# Sheet1.net
KiCad netlist of a schematic drawn in Altium Designer
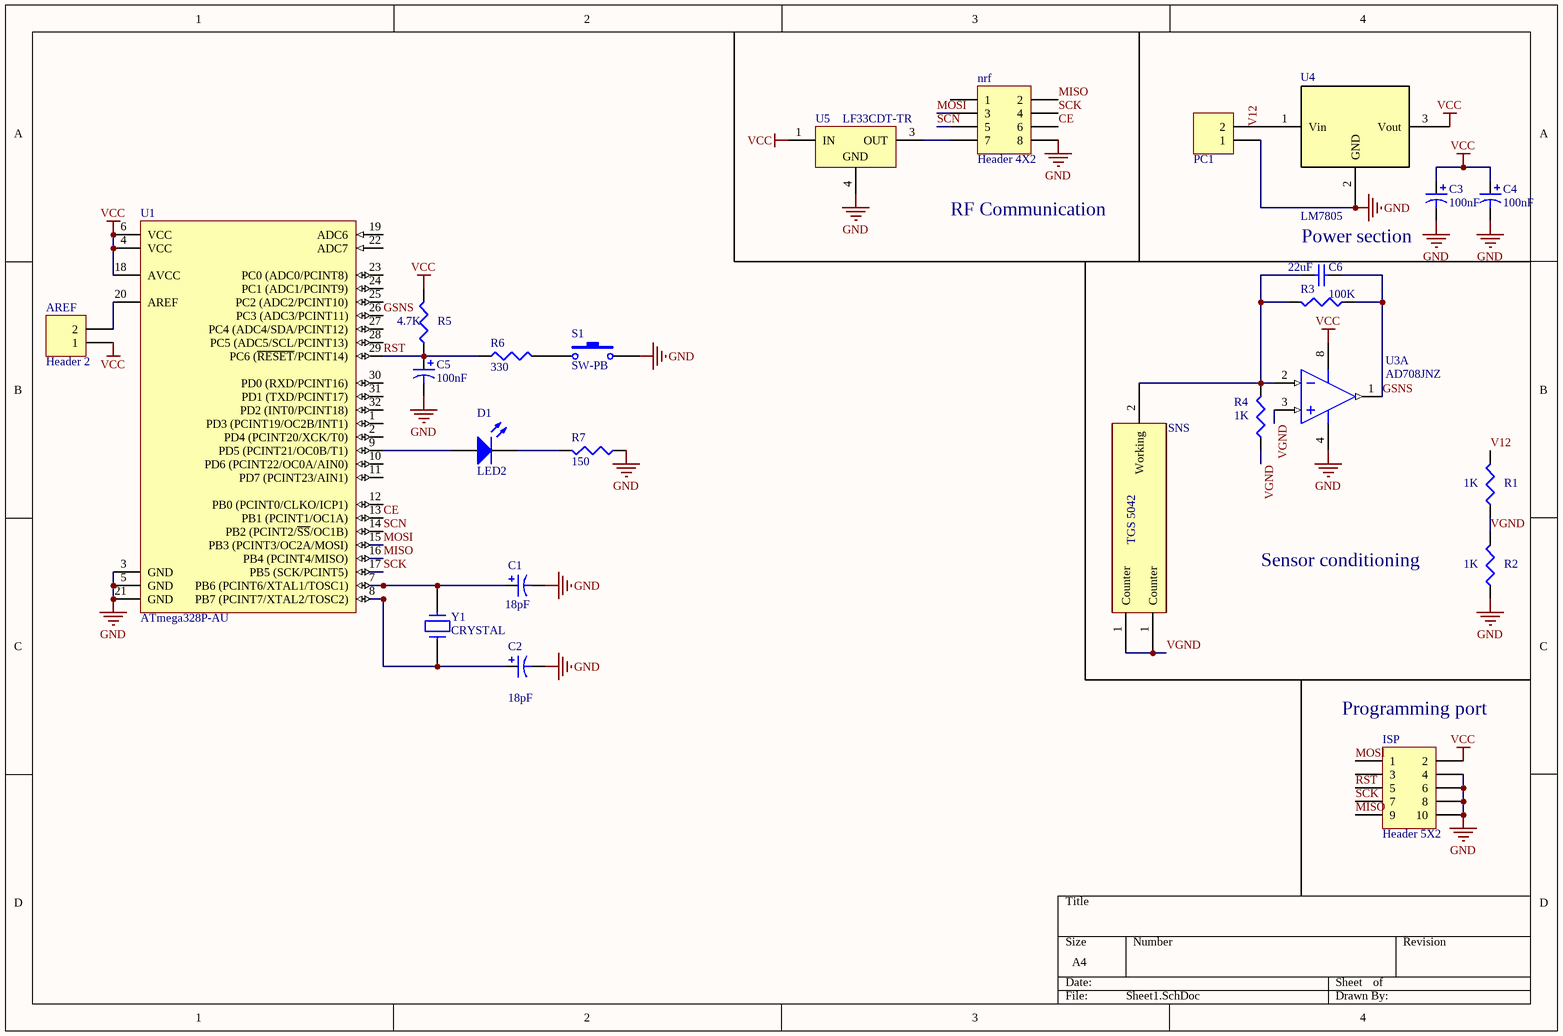
[diagram p0: Sheet1.SchDoc]

(export (version "E")
  (design (tool "Eeschema 10.0.6"))
  (components
    (comp (ref "AREF")
      (value "Header 2")
      (footprint "HDR1X2")
      (description "Header, 2-Pin")
      (fields (field (name "PUBLISHER") "Altium Limited"))
      (libsource (lib "IOT_UNI_VER1") (part "Header 2"))
    )
    (comp (ref "C1")
      (value "18pF")
      (footprint "Resistor")
      (description "Polarized Capacitor (Surface Mount)")
      (fields (field (name "Comment") "Cap Pol3") (field (name "PUBLISHER") "Altium Limited"))
      (libsource (lib "IOT_UNI_VER1") (part "Cap Pol3"))
    )
    (comp (ref "C2")
      (value "18pF")
      (footprint "Resistor")
      (description "Polarized Capacitor (Surface Mount)")
      (fields (field (name "Comment") "Cap Pol3") (field (name "PUBLISHER") "Altium Limited"))
      (libsource (lib "IOT_UNI_VER1") (part "Cap Pol3"))
    )
    (comp (ref "C3")
      (value "100nF")
      (footprint "Resistor")
      (description "Polarized Capacitor (Surface Mount)")
      (fields (field (name "Comment") "Cap Pol3") (field (name "PUBLISHER") "Altium Limited"))
      (libsource (lib "IOT_UNI_VER1") (part "Cap Pol3"))
    )
    (comp (ref "C4")
      (value "100nF")
      (footprint "Resistor")
      (description "Polarized Capacitor (Surface Mount)")
      (fields (field (name "Comment") "Cap Pol3") (field (name "PUBLISHER") "Altium Limited"))
      (libsource (lib "IOT_UNI_VER1") (part "Cap Pol3"))
    )
    (comp (ref "C5")
      (value "100nF")
      (footprint "Resistor")
      (description "Polarized Capacitor (Surface Mount)")
      (fields (field (name "Comment") "Cap Pol3") (field (name "PUBLISHER") "Altium Limited"))
      (libsource (lib "IOT_UNI_VER1") (part "Cap Pol3"))
    )
    (comp (ref "C6")
      (value "22uF")
      (footprint "RB.1/.3")
      (description "Capacitor (Semiconductor SIM Model)")
      (fields (field (name "PUBLISHER") "Altium Limited"))
      (libsource (lib "Devices") (part "Cap Semi"))
    )
    (comp (ref "D1")
      (value "LED2")
      (footprint "3.2X1.6X1.1")
      (description "Typical RED, GREEN, YELLOW, AMBER GaAs LED")
      (fields (field (name "PUBLISHER") "Altium Limited"))
      (libsource (lib "Miscellaneous Devices") (part "LED2"))
    )
    (comp (ref "ISP")
      (value "Header 5X2")
      (footprint "HDR2X5")
      (description "Header, 5-Pin, Dual row")
      (fields (field (name "PUBLISHER") "Altium Limited"))
      (libsource (lib "IOT_UNI_VER1") (part "Header 5X2"))
    )
    (comp (ref "nrf")
      (value "Header 4X2")
      (footprint "HDR2X4")
      (description "Header, 4-Pin, Dual row")
      (fields (field (name "PUBLISHER") "Altium Limited"))
      (libsource (lib "IOT_UNI_VER1") (part "Header 4X2"))
    )
    (comp (ref "PC1")
      (value "Power Connector")
      (footprint "My_ Power_Connector")
      (description "white Power Connector")
      (libsource (lib "Altium library (www.AVRelec.com)") (part "Power Connector"))
    )
    (comp (ref "R1")
      (value "1K")
      (footprint "Resistor")
      (description "Resistor")
      (fields (field (name "Comment") "Rsepehr") (field (name "PUBLISHER") "Altium Limited"))
      (libsource (lib "IOT_UNI_VER1") (part "Res3"))
    )
    (comp (ref "R2")
      (value "1K")
      (footprint "Resistor")
      (description "Resistor")
      (fields (field (name "Comment") "Rsepehr") (field (name "PUBLISHER") "Altium Limited"))
      (libsource (lib "IOT_UNI_VER1") (part "Res3"))
    )
    (comp (ref "R3")
      (value "100K")
      (footprint "Resistor")
      (description "Resistor")
      (fields (field (name "Comment") "Rsepehr") (field (name "PUBLISHER") "Altium Limited"))
      (libsource (lib "IOT_UNI_VER1") (part "Res3"))
    )
    (comp (ref "R4")
      (value "1K")
      (footprint "Resistor")
      (description "Resistor")
      (fields (field (name "Comment") "Rsepehr") (field (name "PUBLISHER") "Altium Limited"))
      (libsource (lib "IOT_UNI_VER1") (part "Res3"))
    )
    (comp (ref "R5")
      (value "4.7K")
      (footprint "Resistor")
      (description "Resistor")
      (fields (field (name "Comment") "Rsepehr") (field (name "PUBLISHER") "Altium Limited"))
      (libsource (lib "IOT_UNI_VER1") (part "Res3"))
    )
    (comp (ref "R6")
      (value "330")
      (footprint "Resistor")
      (description "Resistor")
      (fields (field (name "Comment") "Rsepehr") (field (name "PUBLISHER") "Altium Limited"))
      (libsource (lib "IOT_UNI_VER1") (part "Res3"))
    )
    (comp (ref "R7")
      (value "150")
      (footprint "Resistor")
      (description "Resistor")
      (fields (field (name "Comment") "Rsepehr") (field (name "PUBLISHER") "Altium Limited"))
      (libsource (lib "IOT_UNI_VER1") (part "Res3"))
    )
    (comp (ref "S1")
      (value "SW-PB")
      (footprint "SPST-2")
      (description "Switch")
      (fields (field (name "PUBLISHER") "Altium Limited"))
      (libsource (lib "Miscellaneous Devices") (part "SW-PB"))
    )
    (comp (ref "SNS")
      (value "Component_1")
      (footprint "GSPAK")
      (libsource (lib "TGS 5042") (part "Component_1"))
    )
    (comp (ref "U1")
      (value "ATmega328P-AU")
      (footprint "32A_N")
      (libsource (lib "Atmel Microcontroller megaAVR") (part "ATmega328P-AU"))
    )
    (comp (ref "U3")
      (value "AD708JNZ")
      (footprint "ADI-N-8")
      (fields (field (name "GENERIC PART NUMBER") "AD708") (field (name "MANUFACTURER") "Analog Devices"))
      (libsource (lib "Analog Devices Operational Amplifiers") (part "AD708JNZ"))
    )
    (comp (ref "U4") (value "LM7805") (footprint "TO-220") (libsource (lib "LM7805") (part "Component_1")))
    (comp (ref "U5")
      (value "LF33CDT-TR")
      (footprint "TO-252_N")
      (description "500mA, Very Low Drop (0.45V) Voltage Regulator, 3.3V, 3-Pin DPAK, Tape and Reel")
      (libsource (lib "STMicroelectronics Power Management Linear Regulator") (part "LF33CDT-TR"))
    )
    (comp (ref "Y1")
      (value "CRYSTAL")
      (footprint "My_Crystal")
      (description "Crystal")
      (libsource (lib "IOT_UNI_VER1") (part "CRYSTAL"))
    )
  )
  (nets
    (net (code "1") (name "/CE") (class "Default")
      (node (ref "U1") (pin "13") (pinfunction "PB1_(PCINT1/OC1A)_13") (pintype "bidirectional"))
      (node (ref "nrf") (pin "6") (pinfunction "6_6") (pintype "passive"))
    )
    (net (code "2") (name "/GSNS") (class "Default")
      (node (ref "C6") (pin "2") (pinfunction "2_2") (pintype "passive"))
      (node (ref "R3") (pin "1") (pinfunction "1_1") (pintype "passive"))
      (node (ref "U1") (pin "26") (pinfunction "PC3_(ADC3/PCINT11)_26") (pintype "bidirectional"))
      (node (ref "U3") (pin "1") (pinfunction "OUT_A_1") (pintype "output"))
    )
    (net (code "3") (name "/MISO") (class "Default")
      (node (ref "ISP") (pin "9") (pinfunction "9_9") (pintype "passive"))
      (node (ref "U1") (pin "16") (pinfunction "PB4_(PCINT4/MISO)_16") (pintype "bidirectional"))
      (node (ref "nrf") (pin "2") (pinfunction "2_2") (pintype "passive"))
    )
    (net (code "4") (name "/MOSI") (class "Default")
      (node (ref "ISP") (pin "1") (pinfunction "1_1") (pintype "passive"))
      (node (ref "U1") (pin "15") (pinfunction "PB3_(PCINT3/OC2A/MOSI)_15") (pintype "bidirectional"))
      (node (ref "nrf") (pin "3") (pinfunction "3_3") (pintype "passive"))
    )
    (net (code "5") (name "/RST") (class "Default")
      (node (ref "C5") (pin "1") (pinfunction "1_1") (pintype "passive"))
      (node (ref "ISP") (pin "5") (pinfunction "5_5") (pintype "passive"))
      (node (ref "R5") (pin "1") (pinfunction "1_1") (pintype "passive"))
      (node (ref "R6") (pin "1") (pinfunction "1_1") (pintype "passive"))
      (node (ref "U1") (pin "29") (pinfunction "PC6_(~{RESET}/PCINT14)_29") (pintype "bidirectional"))
    )
    (net (code "6") (name "/SCK") (class "Default")
      (node (ref "ISP") (pin "7") (pinfunction "7_7") (pintype "passive"))
      (node (ref "U1") (pin "17") (pinfunction "PB5_(SCK/PCINT5)_17") (pintype "bidirectional"))
      (node (ref "nrf") (pin "4") (pinfunction "4_4") (pintype "passive"))
    )
    (net (code "7") (name "/SCN") (class "Default")
      (node (ref "U1") (pin "14") (pinfunction "PB2_(PCINT2/~{SS}/OC1B)_14") (pintype "bidirectional"))
      (node (ref "nrf") (pin "5") (pinfunction "5_5") (pintype "passive"))
    )
    (net (code "8") (name "/V12") (class "Default")
      (node (ref "PC1") (pin "2") (pinfunction "2_2") (pintype "passive"))
      (node (ref "R1") (pin "2") (pinfunction "2_2") (pintype "passive"))
      (node (ref "U4") (pin "1") (pinfunction "Vin_1") (pintype "passive"))
    )
    (net (code "9") (name "/VGND") (class "Default")
      (node (ref "R1") (pin "1") (pinfunction "1_1") (pintype "passive"))
      (node (ref "R2") (pin "2") (pinfunction "2_2") (pintype "passive"))
      (node (ref "R4") (pin "1") (pinfunction "1_1") (pintype "passive"))
      (node (ref "SNS") (pin "1") (pinfunction "Counter_1") (pintype "passive"))
      (node (ref "U3") (pin "3") (pinfunction "+IN_A_3") (pintype "input"))
    )
    (net (code "10") (name "GND") (class "Default")
      (node (ref "C1") (pin "2") (pinfunction "2_2") (pintype "passive"))
      (node (ref "C2") (pin "2") (pinfunction "2_2") (pintype "passive"))
      (node (ref "C3") (pin "2") (pinfunction "2_2") (pintype "passive"))
      (node (ref "C4") (pin "2") (pinfunction "2_2") (pintype "passive"))
      (node (ref "C5") (pin "2") (pinfunction "2_2") (pintype "passive"))
      (node (ref "ISP") (pin "10") (pinfunction "10_10") (pintype "passive"))
      (node (ref "ISP") (pin "4") (pinfunction "4_4") (pintype "passive"))
      (node (ref "ISP") (pin "6") (pinfunction "6_6") (pintype "passive"))
      (node (ref "ISP") (pin "8") (pinfunction "8_8") (pintype "passive"))
      (node (ref "PC1") (pin "1") (pinfunction "1_1") (pintype "passive"))
      (node (ref "R2") (pin "1") (pinfunction "1_1") (pintype "passive"))
      (node (ref "R7") (pin "1") (pinfunction "1_1") (pintype "passive"))
      (node (ref "S1") (pin "2") (pinfunction "2_2") (pintype "passive"))
      (node (ref "U1") (pin "21") (pinfunction "GND_21") (pintype "power_in"))
      (node (ref "U1") (pin "3") (pinfunction "GND_3") (pintype "power_in"))
      (node (ref "U1") (pin "5") (pinfunction "GND_5") (pintype "power_in"))
      (node (ref "U3") (pin "4") (pinfunction "-VS_4") (pintype "power_in"))
      (node (ref "U4") (pin "2") (pinfunction "GND_2") (pintype "passive"))
      (node (ref "U5") (pin "4") (pinfunction "GND_4") (pintype "power_in"))
      (node (ref "nrf") (pin "8") (pinfunction "8_8") (pintype "passive"))
    )
    (net (code "11") (name "Net-(D1-A)") (class "Default")
      (node (ref "D1") (pin "1") (pinfunction "A_1") (pintype "passive"))
      (node (ref "U1") (pin "9") (pinfunction "PD5_(PCINT21/OC0B/T1)_9") (pintype "bidirectional"))
    )
    (net (code "12") (name "Net-(D1-K)") (class "Default")
      (node (ref "D1") (pin "2") (pinfunction "K_2") (pintype "passive"))
      (node (ref "R7") (pin "2") (pinfunction "2_2") (pintype "passive"))
    )
    (net (code "13") (name "Net-(R6-Pad2)") (class "Default")
      (node (ref "R6") (pin "2") (pinfunction "2_2") (pintype "passive"))
      (node (ref "S1") (pin "1") (pinfunction "1_1") (pintype "passive"))
    )
    (net (code "14") (name "Net-(SNS-Working)") (class "Default")
      (node (ref "C6") (pin "1") (pinfunction "1_1") (pintype "passive"))
      (node (ref "R3") (pin "2") (pinfunction "2_2") (pintype "passive"))
      (node (ref "R4") (pin "2") (pinfunction "2_2") (pintype "passive"))
      (node (ref "SNS") (pin "2") (pinfunction "Working_2") (pintype "passive"))
      (node (ref "U3") (pin "2") (pinfunction "-IN_A_2") (pintype "input"))
    )
    (net (code "15") (name "Net-(U1-AREF)") (class "Default")
      (node (ref "AREF") (pin "2") (pinfunction "2_2") (pintype "passive"))
      (node (ref "U1") (pin "20") (pinfunction "AREF_20") (pintype "passive"))
    )
    (net (code "16") (name "Net-(U1-PB6_(PCINT6{slash}XTAL1{slash}TOSC1))") (class "Default")
      (node (ref "C1") (pin "1") (pinfunction "1_1") (pintype "passive"))
      (node (ref "U1") (pin "7") (pinfunction "PB6_(PCINT6/XTAL1/TOSC1)_7") (pintype "bidirectional"))
      (node (ref "Y1") (pin "2") (pinfunction "2_2") (pintype "passive"))
    )
    (net (code "17") (name "Net-(U1-PB7_(PCINT7{slash}XTAL2{slash}TOSC2))") (class "Default")
      (node (ref "C2") (pin "1") (pinfunction "1_1") (pintype "passive"))
      (node (ref "U1") (pin "8") (pinfunction "PB7_(PCINT7/XTAL2/TOSC2)_8") (pintype "bidirectional"))
      (node (ref "Y1") (pin "1") (pinfunction "1_1") (pintype "passive"))
    )
    (net (code "18") (name "Net-(U5-OUT)") (class "Default")
      (node (ref "U5") (pin "3") (pinfunction "OUT_3") (pintype "power_in"))
      (node (ref "nrf") (pin "7") (pinfunction "7_7") (pintype "passive"))
    )
    (net (code "19") (name "VCC") (class "Default")
      (node (ref "AREF") (pin "1") (pinfunction "1_1") (pintype "passive"))
      (node (ref "C3") (pin "1") (pinfunction "1_1") (pintype "passive"))
      (node (ref "C4") (pin "1") (pinfunction "1_1") (pintype "passive"))
      (node (ref "ISP") (pin "2") (pinfunction "2_2") (pintype "passive"))
      (node (ref "R5") (pin "2") (pinfunction "2_2") (pintype "passive"))
      (node (ref "U1") (pin "18") (pinfunction "AVCC_18") (pintype "power_in"))
      (node (ref "U1") (pin "4") (pinfunction "VCC_4") (pintype "power_in"))
      (node (ref "U1") (pin "6") (pinfunction "VCC_6") (pintype "power_in"))
      (node (ref "U3") (pin "8") (pinfunction "+VS_8") (pintype "power_in"))
      (node (ref "U4") (pin "3") (pinfunction "Vout_3") (pintype "passive"))
      (node (ref "U5") (pin "1") (pinfunction "IN_1") (pintype "power_in"))
    )
    (net (code "20") (name "unconnected-(ISP-Pad3)") (class "Default")
      (node (ref "ISP") (pin "3") (pinfunction "3_3") (pintype "passive"))
    )
    (net (code "21") (name "unconnected-(U1-ADC6-Pad19)") (class "Default")
      (node (ref "U1") (pin "19") (pinfunction "ADC6_19") (pintype "input"))
    )
    (net (code "22") (name "unconnected-(U1-ADC7-Pad22)") (class "Default")
      (node (ref "U1") (pin "22") (pinfunction "ADC7_22") (pintype "input"))
    )
    (net (code "23") (name "unconnected-(U1-PB0_(PCINT0{slash}CLKO{slash}ICP1)-Pad12)") (class "Default")
      (node (ref "U1") (pin "12") (pinfunction "PB0_(PCINT0/CLKO/ICP1)_12") (pintype "bidirectional"))
    )
    (net (code "24") (name "unconnected-(U1-PC0_(ADC0{slash}PCINT8)-Pad23)") (class "Default")
      (node (ref "U1") (pin "23") (pinfunction "PC0_(ADC0/PCINT8)_23") (pintype "bidirectional"))
    )
    (net (code "25") (name "unconnected-(U1-PC1_(ADC1{slash}PCINT9)-Pad24)") (class "Default")
      (node (ref "U1") (pin "24") (pinfunction "PC1_(ADC1/PCINT9)_24") (pintype "bidirectional"))
    )
    (net (code "26") (name "unconnected-(U1-PC2_(ADC2{slash}PCINT10)-Pad25)") (class "Default")
      (node (ref "U1") (pin "25") (pinfunction "PC2_(ADC2/PCINT10)_25") (pintype "bidirectional"))
    )
    (net (code "27") (name "unconnected-(U1-PC4_(ADC4{slash}SDA{slash}PCINT12)-Pad27)") (class "Default")
      (node (ref "U1") (pin "27") (pinfunction "PC4_(ADC4/SDA/PCINT12)_27") (pintype "bidirectional"))
    )
    (net (code "28") (name "unconnected-(U1-PC5_(ADC5{slash}SCL{slash}PCINT13)-Pad28)") (class "Default")
      (node (ref "U1") (pin "28") (pinfunction "PC5_(ADC5/SCL/PCINT13)_28") (pintype "bidirectional"))
    )
    (net (code "29") (name "unconnected-(U1-PD0_(RXD{slash}PCINT16)-Pad30)") (class "Default")
      (node (ref "U1") (pin "30") (pinfunction "PD0_(RXD/PCINT16)_30") (pintype "bidirectional"))
    )
    (net (code "30") (name "unconnected-(U1-PD1_(TXD{slash}PCINT17)-Pad31)") (class "Default")
      (node (ref "U1") (pin "31") (pinfunction "PD1_(TXD/PCINT17)_31") (pintype "bidirectional"))
    )
    (net (code "31") (name "unconnected-(U1-PD2_(INT0{slash}PCINT18)-Pad32)") (class "Default")
      (node (ref "U1") (pin "32") (pinfunction "PD2_(INT0/PCINT18)_32") (pintype "bidirectional"))
    )
    (net (code "32") (name "unconnected-(U1-PD3_(PCINT19{slash}OC2B{slash}INT1)-Pad1)") (class "Default")
      (node (ref "U1") (pin "1") (pinfunction "PD3_(PCINT19/OC2B/INT1)_1") (pintype "bidirectional"))
    )
    (net (code "33") (name "unconnected-(U1-PD4_(PCINT20{slash}XCK{slash}T0)-Pad2)") (class "Default")
      (node (ref "U1") (pin "2") (pinfunction "PD4_(PCINT20/XCK/T0)_2") (pintype "bidirectional"))
    )
    (net (code "34") (name "unconnected-(U1-PD6_(PCINT22{slash}OC0A{slash}AIN0)-Pad10)") (class "Default")
      (node (ref "U1") (pin "10") (pinfunction "PD6_(PCINT22/OC0A/AIN0)_10") (pintype "bidirectional"))
    )
    (net (code "35") (name "unconnected-(U1-PD7_(PCINT23{slash}AIN1)-Pad11)") (class "Default")
      (node (ref "U1") (pin "11") (pinfunction "PD7_(PCINT23/AIN1)_11") (pintype "bidirectional"))
    )
    (net (code "36") (name "unconnected-(nrf-Pad1)") (class "Default")
      (node (ref "nrf") (pin "1") (pinfunction "1_1") (pintype "passive"))
    )
  )
)
